# FD_Capacitance_Sensor_v19.net
KiCad netlist of a schematic drawn in EAGLE
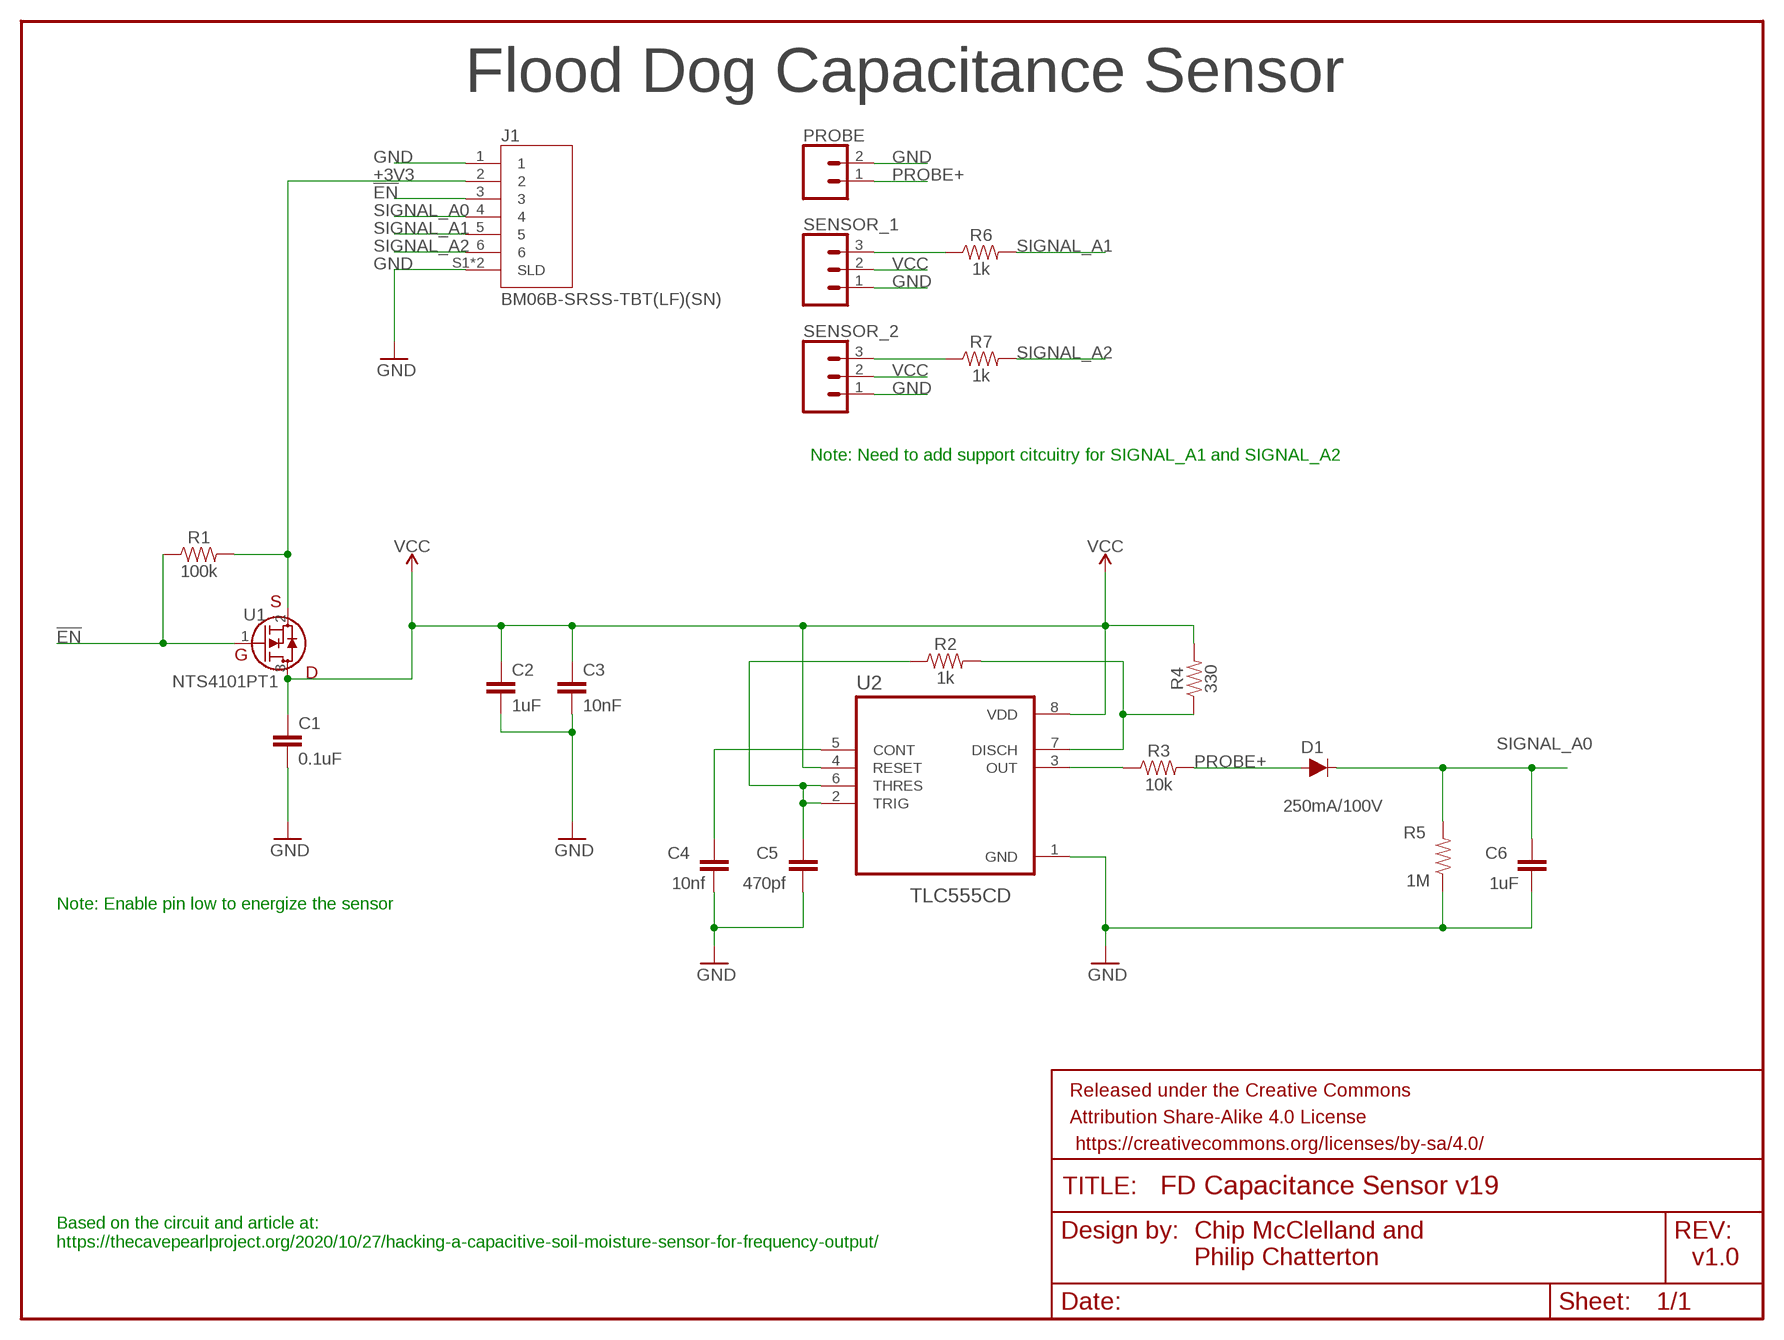
[diagram p0: schematic, sheet 1]

(export (version "E")
  (design (tool "Eeschema 10.0.6"))
  (components
    (comp (ref "C1")
      (value "0.1uF")
      (footprint "eagle-import:0805@1")
      (fields (field (name "HOUSEPART") "YES") (field (name "MPN") "MF-CAP-0805-0.1uF"))
      (libsource (lib "eagle-import") (part "CAP-MF-0.1UF-0805"))
    )
    (comp (ref "C2")
      (value "1uF")
      (footprint "eagle-import:0805@1")
      (fields (field (name "HOUSEPART") "yes") (field (name "MPN") "MF-CAP-0805-1uF"))
      (libsource (lib "eagle-import") (part "CAP-MF-1UF-0805"))
    )
    (comp (ref "C3")
      (value "10nF")
      (footprint "eagle-import:0805@1")
      (fields (field (name "HOUSEPART") "NO") (field (name "MPN") "C0805X103K1RAC3316"))
      (libsource (lib "eagle-import") (part "CAP-10NF-0805"))
    )
    (comp (ref "C4")
      (value "10nf")
      (footprint "eagle-import:C0805")
      (libsource (lib "eagle-import") (part "C-EUC0805"))
    )
    (comp (ref "C5")
      (value "470pf")
      (footprint "eagle-import:C0805")
      (libsource (lib "eagle-import") (part "C-EUC0805"))
    )
    (comp (ref "C6")
      (value "1uF")
      (footprint "eagle-import:C0805")
      (libsource (lib "eagle-import") (part "C-EUC0805"))
    )
    (comp (ref "D1")
      (value "250mA/100V")
      (footprint "eagle-import:SOD-323")
      (fields (field (name "MPN") "BAS16HT1G"))
      (libsource (lib "eagle-import") (part "DIODE-BAS16J"))
    )
    (comp (ref "FRAME1")
      (value "FRAME-LETTERNO_PACKAGE")
      (footprint "eagle-import:DUMMY")
      (fields (field (name "DESIGNER") "Nobody"))
      (libsource (lib "eagle-import") (part "FRAME-LETTERNO_PACKAGE"))
    )
    (comp (ref "J1")
      (value "BM06B-SRSS-TBT(LF)(SN)")
      (footprint "eagle-import:JST_BM06B-SRSS-TB(LF)(SN)")
      (libsource (lib "eagle-import") (part "BM06B-SRSS-TBT(LF)(SN)"))
    )
    (comp (ref "PROBE")
      (value "CONN_02")
      (footprint "eagle-import:1X02")
      (libsource (lib "eagle-import") (part "CONN_02"))
    )
    (comp (ref "R1")
      (value "100k")
      (footprint "eagle-import:0805")
      (fields (field (name "MPN") "MF-RES-0805-100K") (field (name "MPN_1") "MF-RES-0805-100K"))
      (libsource (lib "eagle-import") (part "RESISTOR-MF-100K-0805"))
    )
    (comp (ref "R2")
      (value "1k")
      (footprint "eagle-import:0805")
      (fields (field (name "HOUSEPART") "YES") (field (name "MPN") "MF-RES-0805-1K"))
      (libsource (lib "eagle-import") (part "RESISTOR-MF-1K-0805"))
    )
    (comp (ref "R3")
      (value "10k")
      (footprint "eagle-import:0805")
      (fields (field (name "MPN") "MF-RES-0805-10K"))
      (libsource (lib "eagle-import") (part "RESISTOR-MF-10K-0805"))
    )
    (comp (ref "R4")
      (value "330")
      (footprint "eagle-import:0805")
      (fields (field (name "HOUSEPART") "YES") (field (name "MPN") "MF-RES-0805-330"))
      (libsource (lib "eagle-import") (part "RESISTOR-MF-330-0805"))
    )
    (comp (ref "R5")
      (value "1M")
      (footprint "eagle-import:0805")
      (fields (field (name "HOUSEPART") "YES") (field (name "MPN") "MF-RES-0805-1K"))
      (libsource (lib "eagle-import") (part "RESISTOR-MF-1K-0805"))
    )
    (comp (ref "R6")
      (value "1k")
      (footprint "eagle-import:0805")
      (fields (field (name "HOUSEPART") "YES") (field (name "MPN") "MF-RES-0805-1K"))
      (libsource (lib "eagle-import") (part "RESISTOR-MF-1K-0805"))
    )
    (comp (ref "R7")
      (value "1k")
      (footprint "eagle-import:0805")
      (fields (field (name "HOUSEPART") "YES") (field (name "MPN") "MF-RES-0805-1K"))
      (libsource (lib "eagle-import") (part "RESISTOR-MF-1K-0805"))
    )
    (comp (ref "SENSOR_1")
      (value "CONN_03")
      (footprint "eagle-import:1X03")
      (libsource (lib "eagle-import") (part "CONN_03"))
    )
    (comp (ref "SENSOR_2")
      (value "CONN_03")
      (footprint "eagle-import:1X03")
      (libsource (lib "eagle-import") (part "CONN_03"))
    )
    (comp (ref "U1")
      (value "NTS4101PT1")
      (footprint "eagle-import:SOT_101PT1_ONS")
      (libsource (lib "eagle-import") (part "NTS4101PT1"))
    )
    (comp (ref "U2")
      (value "TLC555CD")
      (footprint "eagle-import:SOIC127P599X175-8N")
      (fields (field (name "DIGI-KEY_PART_NUMBER") "296-52992-ND") (field (name "MF") "Texas Instruments"))
      (libsource (lib "eagle-import") (part "TLC555CD"))
    )
  )
  (nets
    (net (code "1") (name "/+3V3") (class "Default")
      (node (ref "J1") (pin "2") (pinfunction "2_2") (pintype "passive"))
      (node (ref "R1") (pin "2") (pinfunction "2_2") (pintype "passive"))
      (node (ref "U1") (pin "2") (pinfunction "S_2") (pintype "passive"))
    )
    (net (code "2") (name "/PROBE+") (class "Default")
      (node (ref "D1") (pin "A") (pinfunction "A_A") (pintype "passive"))
      (node (ref "PROBE") (pin "1") (pinfunction "1_1") (pintype "passive"))
      (node (ref "R3") (pin "2") (pinfunction "2_2") (pintype "passive"))
    )
    (net (code "3") (name "/SIGNAL_A0") (class "Default")
      (node (ref "C6") (pin "2") (pinfunction "2_2") (pintype "passive"))
      (node (ref "D1") (pin "C") (pinfunction "C_C") (pintype "passive"))
      (node (ref "J1") (pin "4") (pinfunction "4_4") (pintype "passive"))
      (node (ref "R5") (pin "2") (pinfunction "2_2") (pintype "passive"))
    )
    (net (code "4") (name "/SIGNAL_A1") (class "Default")
      (node (ref "J1") (pin "5") (pinfunction "5_5") (pintype "passive"))
      (node (ref "R6") (pin "2") (pinfunction "2_2") (pintype "passive"))
    )
    (net (code "5") (name "/SIGNAL_A2") (class "Default")
      (node (ref "J1") (pin "6") (pinfunction "6_6") (pintype "passive"))
      (node (ref "R7") (pin "2") (pinfunction "2_2") (pintype "passive"))
    )
    (net (code "6") (name "/~{EN}") (class "Default")
      (node (ref "J1") (pin "3") (pinfunction "3_3") (pintype "passive"))
      (node (ref "R1") (pin "1") (pinfunction "1_1") (pintype "passive"))
      (node (ref "U1") (pin "1") (pinfunction "G_1") (pintype "passive"))
    )
    (net (code "7") (name "GND") (class "Default")
      (node (ref "C1") (pin "2") (pinfunction "2_2") (pintype "passive"))
      (node (ref "C2") (pin "2") (pinfunction "2_2") (pintype "passive"))
      (node (ref "C3") (pin "2") (pinfunction "2_2") (pintype "passive"))
      (node (ref "C4") (pin "1") (pinfunction "1_1") (pintype "passive"))
      (node (ref "C5") (pin "1") (pinfunction "1_1") (pintype "passive"))
      (node (ref "C6") (pin "1") (pinfunction "1_1") (pintype "passive"))
      (node (ref "J1") (pin "1") (pinfunction "1_1") (pintype "passive"))
      (node (ref "J1") (pin "S1") (pinfunction "SLD_S1") (pintype "passive"))
      (node (ref "J1") (pin "S2") (pinfunction "SLD_S2") (pintype "passive"))
      (node (ref "PROBE") (pin "2") (pinfunction "2_2") (pintype "passive"))
      (node (ref "R5") (pin "1") (pinfunction "1_1") (pintype "passive"))
      (node (ref "SENSOR_1") (pin "1") (pinfunction "1_1") (pintype "passive"))
      (node (ref "SENSOR_2") (pin "1") (pinfunction "1_1") (pintype "passive"))
      (node (ref "U2") (pin "1") (pinfunction "GND_1") (pintype "power_in"))
    )
    (net (code "8") (name "Net-(R6-Pad1)") (class "Default")
      (node (ref "R6") (pin "1") (pinfunction "1_1") (pintype "passive"))
      (node (ref "SENSOR_1") (pin "3") (pinfunction "3_3") (pintype "passive"))
    )
    (net (code "9") (name "Net-(R7-Pad1)") (class "Default")
      (node (ref "R7") (pin "1") (pinfunction "1_1") (pintype "passive"))
      (node (ref "SENSOR_2") (pin "3") (pinfunction "3_3") (pintype "passive"))
    )
    (net (code "10") (name "Net-(U2-CONT)") (class "Default")
      (node (ref "C4") (pin "2") (pinfunction "2_2") (pintype "passive"))
      (node (ref "U2") (pin "5") (pinfunction "CONT_5") (pintype "input"))
    )
    (net (code "11") (name "Net-(U2-DISCH)") (class "Default")
      (node (ref "R2") (pin "2") (pinfunction "2_2") (pintype "passive"))
      (node (ref "R4") (pin "1") (pinfunction "1_1") (pintype "passive"))
      (node (ref "U2") (pin "7") (pinfunction "DISCH_7") (pintype "output"))
    )
    (net (code "12") (name "Net-(U2-OUT)") (class "Default")
      (node (ref "R3") (pin "1") (pinfunction "1_1") (pintype "passive"))
      (node (ref "U2") (pin "3") (pinfunction "OUT_3") (pintype "output"))
    )
    (net (code "13") (name "Net-(U2-THRES)") (class "Default")
      (node (ref "C5") (pin "2") (pinfunction "2_2") (pintype "passive"))
      (node (ref "R2") (pin "1") (pinfunction "1_1") (pintype "passive"))
      (node (ref "U2") (pin "2") (pinfunction "TRIG_2") (pintype "input"))
      (node (ref "U2") (pin "6") (pinfunction "THRES_6") (pintype "input"))
    )
    (net (code "14") (name "VCC") (class "Default")
      (node (ref "C1") (pin "1") (pinfunction "1_1") (pintype "passive"))
      (node (ref "C2") (pin "1") (pinfunction "1_1") (pintype "passive"))
      (node (ref "C3") (pin "1") (pinfunction "1_1") (pintype "passive"))
      (node (ref "R4") (pin "2") (pinfunction "2_2") (pintype "passive"))
      (node (ref "SENSOR_1") (pin "2") (pinfunction "2_2") (pintype "passive"))
      (node (ref "SENSOR_2") (pin "2") (pinfunction "2_2") (pintype "passive"))
      (node (ref "U1") (pin "3") (pinfunction "D_3") (pintype "passive"))
      (node (ref "U2") (pin "4") (pinfunction "RESET_4") (pintype "input"))
      (node (ref "U2") (pin "8") (pinfunction "VDD_8") (pintype "power_in"))
    )
  )
)
